# 1bitMux2.net
KiCad netlist of a schematic drawn in Altium Designer
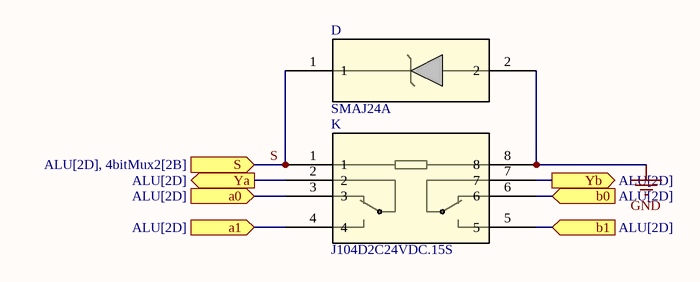
[diagram p0: 1bitMux2.SchDoc]

(export (version "E")
  (design (tool "Eeschema 10.0.6"))
  (components
    (comp (ref "D")
      (value "SMAJ24A")
      (footprint "DI SMAJ24A")
      (description "SMAJ Series 400 W 24 V Uni-Directional Surface Mount TVS Diode - DO-214AC")
      (fields (field (name "MANUFACTURER") "Littelfuse"))
      (libsource (lib "Schlib1") (part "DI SMAJ24A"))
    )
    (comp (ref "K")
      (value "J104D2C24VDC.15S")
      (footprint "Relay J104D2C24VDC.15S")
      (description "Relay Ul Gen Purp DPDT 2C 24VDC")
      (fields (field (name "MANUFACTURER") "CIT Relay & Switch"))
      (libsource (lib "Schlib1") (part "Relay J104D2C24VDC.15S"))
    )
  )
  (nets
    (net (code "1") (name "/S") (class "Default")
      (node (ref "D") (pin "1") (pinfunction "1_1") (pintype "passive"))
      (node (ref "K") (pin "1") (pinfunction "1_1") (pintype "passive"))
    )
    (net (code "2") (name "/Ya") (class "Default")
      (node (ref "K") (pin "2") (pinfunction "2_2") (pintype "passive"))
    )
    (net (code "3") (name "/Yb") (class "Default")
      (node (ref "K") (pin "7") (pinfunction "7_7") (pintype "passive"))
    )
    (net (code "4") (name "/a0") (class "Default")
      (node (ref "K") (pin "3") (pinfunction "3_3") (pintype "passive"))
    )
    (net (code "5") (name "/a1") (class "Default")
      (node (ref "K") (pin "4") (pinfunction "4_4") (pintype "passive"))
    )
    (net (code "6") (name "/b0") (class "Default")
      (node (ref "K") (pin "6") (pinfunction "6_6") (pintype "passive"))
    )
    (net (code "7") (name "/b1") (class "Default")
      (node (ref "K") (pin "5") (pinfunction "5_5") (pintype "passive"))
    )
    (net (code "8") (name "GND") (class "Default")
      (node (ref "D") (pin "2") (pinfunction "2_2") (pintype "passive"))
      (node (ref "K") (pin "8") (pinfunction "8_8") (pintype "passive"))
    )
  )
)
